# EXPS2.net
KiCad netlist of a schematic drawn in EAGLE
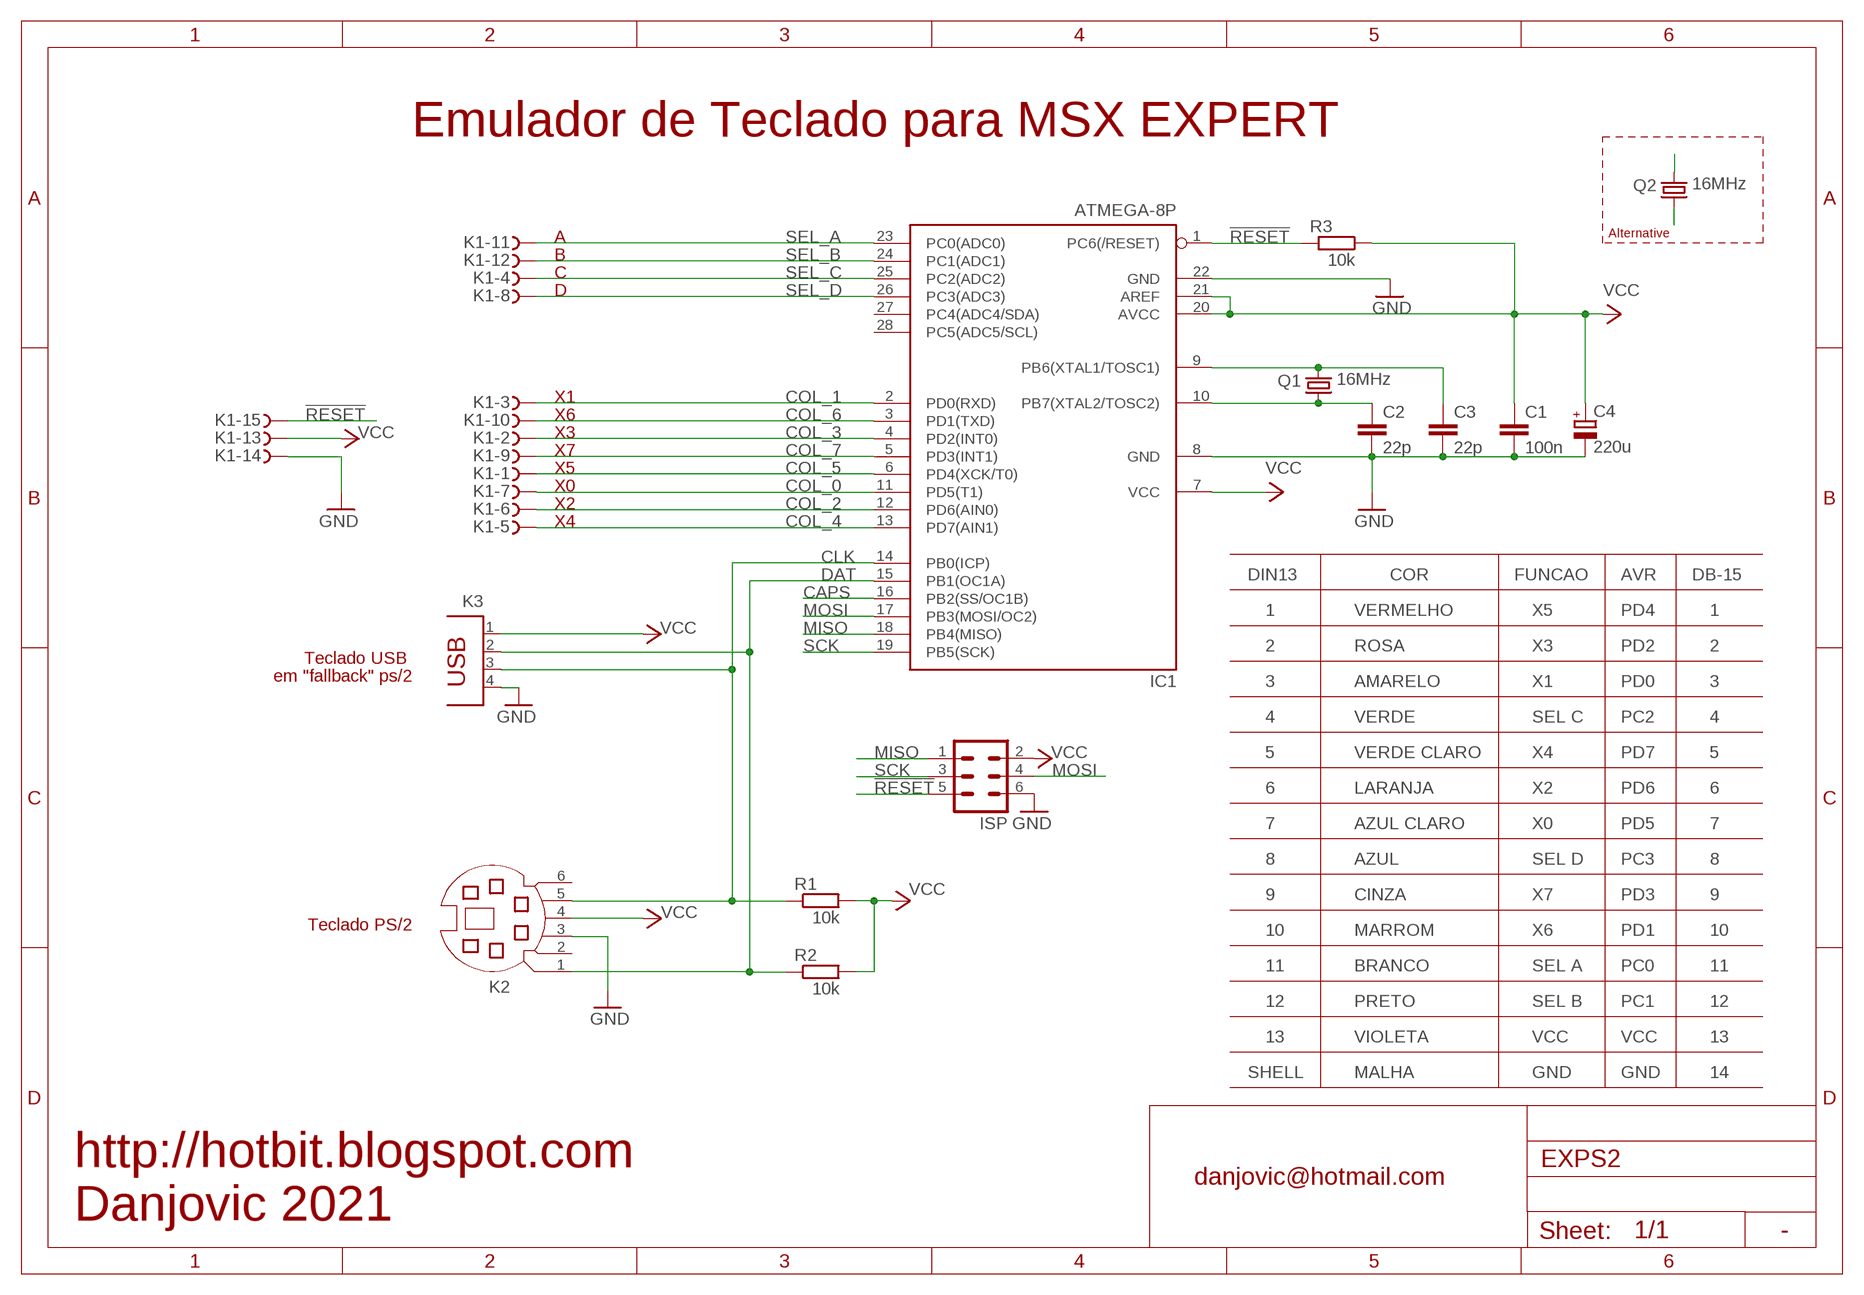
[diagram p0: schematic, sheet 1]

(export (version "E")
  (design (tool "Eeschema 10.0.6"))
  (components
    (comp (ref "C1")
      (value "100n")
      (footprint "eagle-import:C050-024X044")
      (libsource (lib "eagle-import") (part "C-EU050-024X044"))
    )
    (comp (ref "C2")
      (value "22p")
      (footprint "eagle-import:C050-024X044")
      (libsource (lib "eagle-import") (part "C-EU050-024X044"))
    )
    (comp (ref "C3")
      (value "22p")
      (footprint "eagle-import:C050-024X044")
      (libsource (lib "eagle-import") (part "C-EU050-024X044"))
    )
    (comp (ref "C4")
      (value "220u")
      (footprint "eagle-import:E2,5-6")
      (libsource (lib "eagle-import") (part "CPOL-EUE2.5-6"))
    )
    (comp (ref "IC1")
      (value "ATMEGA-8P")
      (footprint "eagle-import:DIL28-3")
      (libsource (lib "eagle-import") (part "MEGA8-P"))
    )
    (comp (ref "ISP")
      (value "ML6")
      (footprint "eagle-import:ML6")
      (libsource (lib "eagle-import") (part "ML6"))
    )
    (comp (ref "K1")
      (value "F15HPS")
      (footprint "eagle-import:F15HP")
      (libsource (lib "eagle-import") (part "F15?SHP"))
    )
    (comp (ref "K2")
      (value "MD06S")
      (footprint "eagle-import:MDIN06S")
      (libsource (lib "eagle-import") (part "MD06S"))
    )
    (comp (ref "K3")
      (value "PN87520")
      (footprint "eagle-import:PN87520")
      (libsource (lib "eagle-import") (part "PN87520"))
    )
    (comp (ref "Q1")
      (value "16MHz")
      (footprint "eagle-import:HC49U-V")
      (libsource (lib "eagle-import") (part "CRYSTALHC49U-V"))
    )
    (comp (ref "Q2")
      (value "16MHz")
      (footprint "eagle-import:TC26H")
      (libsource (lib "eagle-import") (part "CRYSTALTC26H"))
    )
    (comp (ref "R1")
      (value "10k")
      (footprint "eagle-import:0204_7")
      (libsource (lib "eagle-import") (part "R-EU_0204/7"))
    )
    (comp (ref "R2")
      (value "10k")
      (footprint "eagle-import:0204_7")
      (libsource (lib "eagle-import") (part "R-EU_0204/7"))
    )
    (comp (ref "R3")
      (value "10k")
      (footprint "eagle-import:0204_7")
      (libsource (lib "eagle-import") (part "R-EU_0204/7"))
    )
  )
  (nets
    (net (code "1") (name "/CLK") (class "Default")
      (node (ref "IC1") (pin "14") (pinfunction "PB0(ICP)_14") (pintype "bidirectional"))
      (node (ref "K2") (pin "5") (pinfunction "5_5") (pintype "passive"))
      (node (ref "K3") (pin "3") (pinfunction "3_3") (pintype "passive"))
      (node (ref "R1") (pin "1") (pinfunction "1_1") (pintype "passive"))
    )
    (net (code "2") (name "/COL_0") (class "Default")
      (node (ref "IC1") (pin "11") (pinfunction "PD5(T1)_11") (pintype "bidirectional"))
      (node (ref "K1") (pin "7") (pinfunction "F_7") (pintype "passive"))
    )
    (net (code "3") (name "/COL_1") (class "Default")
      (node (ref "IC1") (pin "2") (pinfunction "PD0(RXD)_2") (pintype "bidirectional"))
      (node (ref "K1") (pin "3") (pinfunction "F_3") (pintype "passive"))
    )
    (net (code "4") (name "/COL_2") (class "Default")
      (node (ref "IC1") (pin "12") (pinfunction "PD6(AIN0)_12") (pintype "bidirectional"))
      (node (ref "K1") (pin "6") (pinfunction "F_6") (pintype "passive"))
    )
    (net (code "5") (name "/COL_3") (class "Default")
      (node (ref "IC1") (pin "4") (pinfunction "PD2(INT0)_4") (pintype "bidirectional"))
      (node (ref "K1") (pin "2") (pinfunction "F_2") (pintype "passive"))
    )
    (net (code "6") (name "/COL_4") (class "Default")
      (node (ref "IC1") (pin "13") (pinfunction "PD7(AIN1)_13") (pintype "bidirectional"))
      (node (ref "K1") (pin "5") (pinfunction "F_5") (pintype "passive"))
    )
    (net (code "7") (name "/COL_5") (class "Default")
      (node (ref "IC1") (pin "6") (pinfunction "PD4(XCK/T0)_6") (pintype "bidirectional"))
      (node (ref "K1") (pin "1") (pinfunction "F_1") (pintype "passive"))
    )
    (net (code "8") (name "/COL_6") (class "Default")
      (node (ref "IC1") (pin "3") (pinfunction "PD1(TXD)_3") (pintype "bidirectional"))
      (node (ref "K1") (pin "10") (pinfunction "F_10") (pintype "passive"))
    )
    (net (code "9") (name "/COL_7") (class "Default")
      (node (ref "IC1") (pin "5") (pinfunction "PD3(INT1)_5") (pintype "bidirectional"))
      (node (ref "K1") (pin "9") (pinfunction "F_9") (pintype "passive"))
    )
    (net (code "10") (name "/DAT") (class "Default")
      (node (ref "IC1") (pin "15") (pinfunction "PB1(OC1A)_15") (pintype "bidirectional"))
      (node (ref "K2") (pin "1") (pinfunction "1_1") (pintype "passive"))
      (node (ref "K3") (pin "2") (pinfunction "2_2") (pintype "passive"))
      (node (ref "R2") (pin "1") (pinfunction "1_1") (pintype "passive"))
    )
    (net (code "11") (name "/MISO") (class "Default")
      (node (ref "IC1") (pin "18") (pinfunction "PB4(MISO)_18") (pintype "bidirectional"))
      (node (ref "ISP") (pin "1") (pinfunction "1_1") (pintype "passive"))
    )
    (net (code "12") (name "/MOSI") (class "Default")
      (node (ref "IC1") (pin "17") (pinfunction "PB3(MOSI/OC2)_17") (pintype "bidirectional"))
      (node (ref "ISP") (pin "4") (pinfunction "4_4") (pintype "passive"))
    )
    (net (code "13") (name "/SCK") (class "Default")
      (node (ref "IC1") (pin "19") (pinfunction "PB5(SCK)_19") (pintype "bidirectional"))
      (node (ref "ISP") (pin "3") (pinfunction "3_3") (pintype "passive"))
    )
    (net (code "14") (name "/SEL_A") (class "Default")
      (node (ref "IC1") (pin "23") (pinfunction "PC0(ADC0)_23") (pintype "bidirectional"))
      (node (ref "K1") (pin "11") (pinfunction "F_11") (pintype "passive"))
    )
    (net (code "15") (name "/SEL_B") (class "Default")
      (node (ref "IC1") (pin "24") (pinfunction "PC1(ADC1)_24") (pintype "bidirectional"))
      (node (ref "K1") (pin "12") (pinfunction "F_12") (pintype "passive"))
    )
    (net (code "16") (name "/SEL_C") (class "Default")
      (node (ref "IC1") (pin "25") (pinfunction "PC2(ADC2)_25") (pintype "bidirectional"))
      (node (ref "K1") (pin "4") (pinfunction "F_4") (pintype "passive"))
    )
    (net (code "17") (name "/SEL_D") (class "Default")
      (node (ref "IC1") (pin "26") (pinfunction "PC3(ADC3)_26") (pintype "bidirectional"))
      (node (ref "K1") (pin "8") (pinfunction "F_8") (pintype "passive"))
    )
    (net (code "18") (name "/XTAL1") (class "Default")
      (node (ref "C3") (pin "1") (pinfunction "1_1") (pintype "passive"))
      (node (ref "IC1") (pin "9") (pinfunction "PB6(XTAL1/TOSC1)_9") (pintype "bidirectional"))
      (node (ref "Q1") (pin "2") (pinfunction "2_2") (pintype "passive"))
      (node (ref "Q2") (pin "2") (pinfunction "2_2") (pintype "passive"))
    )
    (net (code "19") (name "/XTAL2") (class "Default")
      (node (ref "C2") (pin "1") (pinfunction "1_1") (pintype "passive"))
      (node (ref "IC1") (pin "10") (pinfunction "PB7(XTAL2/TOSC2)_10") (pintype "bidirectional"))
      (node (ref "Q1") (pin "1") (pinfunction "1_1") (pintype "passive"))
      (node (ref "Q2") (pin "1") (pinfunction "1_1") (pintype "passive"))
    )
    (net (code "20") (name "/~{RESET}") (class "Default")
      (node (ref "IC1") (pin "1") (pinfunction "PC6(/RESET)_1") (pintype "bidirectional"))
      (node (ref "ISP") (pin "5") (pinfunction "5_5") (pintype "passive"))
      (node (ref "K1") (pin "15") (pinfunction "F_15") (pintype "passive"))
      (node (ref "R3") (pin "2") (pinfunction "2_2") (pintype "passive"))
    )
    (net (code "21") (name "GND") (class "Default")
      (node (ref "C1") (pin "2") (pinfunction "2_2") (pintype "passive"))
      (node (ref "C2") (pin "2") (pinfunction "2_2") (pintype "passive"))
      (node (ref "C3") (pin "2") (pinfunction "2_2") (pintype "passive"))
      (node (ref "C4") (pin "-") (pinfunction "-_-") (pintype "passive"))
      (node (ref "IC1") (pin "22") (pinfunction "GND_22") (pintype "power_in"))
      (node (ref "IC1") (pin "8") (pinfunction "GND_8") (pintype "power_in"))
      (node (ref "ISP") (pin "6") (pinfunction "6_6") (pintype "passive"))
      (node (ref "K1") (pin "14") (pinfunction "F_14") (pintype "passive"))
      (node (ref "K2") (pin "3") (pinfunction "3_3") (pintype "passive"))
      (node (ref "K3") (pin "4") (pinfunction "4_4") (pintype "passive"))
    )
    (net (code "22") (name "VCC") (class "Default")
      (node (ref "C1") (pin "1") (pinfunction "1_1") (pintype "passive"))
      (node (ref "C4") (pin "+") (pinfunction "+_+") (pintype "passive"))
      (node (ref "IC1") (pin "20") (pinfunction "AVCC_20") (pintype "power_in"))
      (node (ref "IC1") (pin "21") (pinfunction "AREF_21") (pintype "passive"))
      (node (ref "IC1") (pin "7") (pinfunction "VCC_7") (pintype "power_in"))
      (node (ref "ISP") (pin "2") (pinfunction "2_2") (pintype "passive"))
      (node (ref "K1") (pin "13") (pinfunction "F_13") (pintype "passive"))
      (node (ref "K2") (pin "4") (pinfunction "4_4") (pintype "passive"))
      (node (ref "K3") (pin "1") (pinfunction "1_1") (pintype "passive"))
      (node (ref "R1") (pin "2") (pinfunction "2_2") (pintype "passive"))
      (node (ref "R2") (pin "2") (pinfunction "2_2") (pintype "passive"))
      (node (ref "R3") (pin "1") (pinfunction "1_1") (pintype "passive"))
    )
    (net (code "23") (name "unconnected-(IC1-PB2(SS{slash}OC1B)-Pad16)") (class "Default")
      (node (ref "IC1") (pin "16") (pinfunction "PB2(SS/OC1B)_16") (pintype "bidirectional"))
    )
    (net (code "24") (name "unconnected-(IC1-PC4(ADC4{slash}SDA)-Pad27)") (class "Default")
      (node (ref "IC1") (pin "27") (pinfunction "PC4(ADC4/SDA)_27") (pintype "bidirectional"))
    )
    (net (code "25") (name "unconnected-(IC1-PC5(ADC5{slash}SCL)-Pad28)") (class "Default")
      (node (ref "IC1") (pin "28") (pinfunction "PC5(ADC5/SCL)_28") (pintype "bidirectional"))
    )
    (net (code "26") (name "unconnected-(K2-Pad2)") (class "Default")
      (node (ref "K2") (pin "2") (pinfunction "2_2") (pintype "passive"))
    )
    (net (code "27") (name "unconnected-(K2-Pad6)") (class "Default")
      (node (ref "K2") (pin "6") (pinfunction "6_6") (pintype "passive"))
    )
  )
)
